# TIDA-010056_Page1.net
KiCad netlist of a schematic drawn in Altium Designer
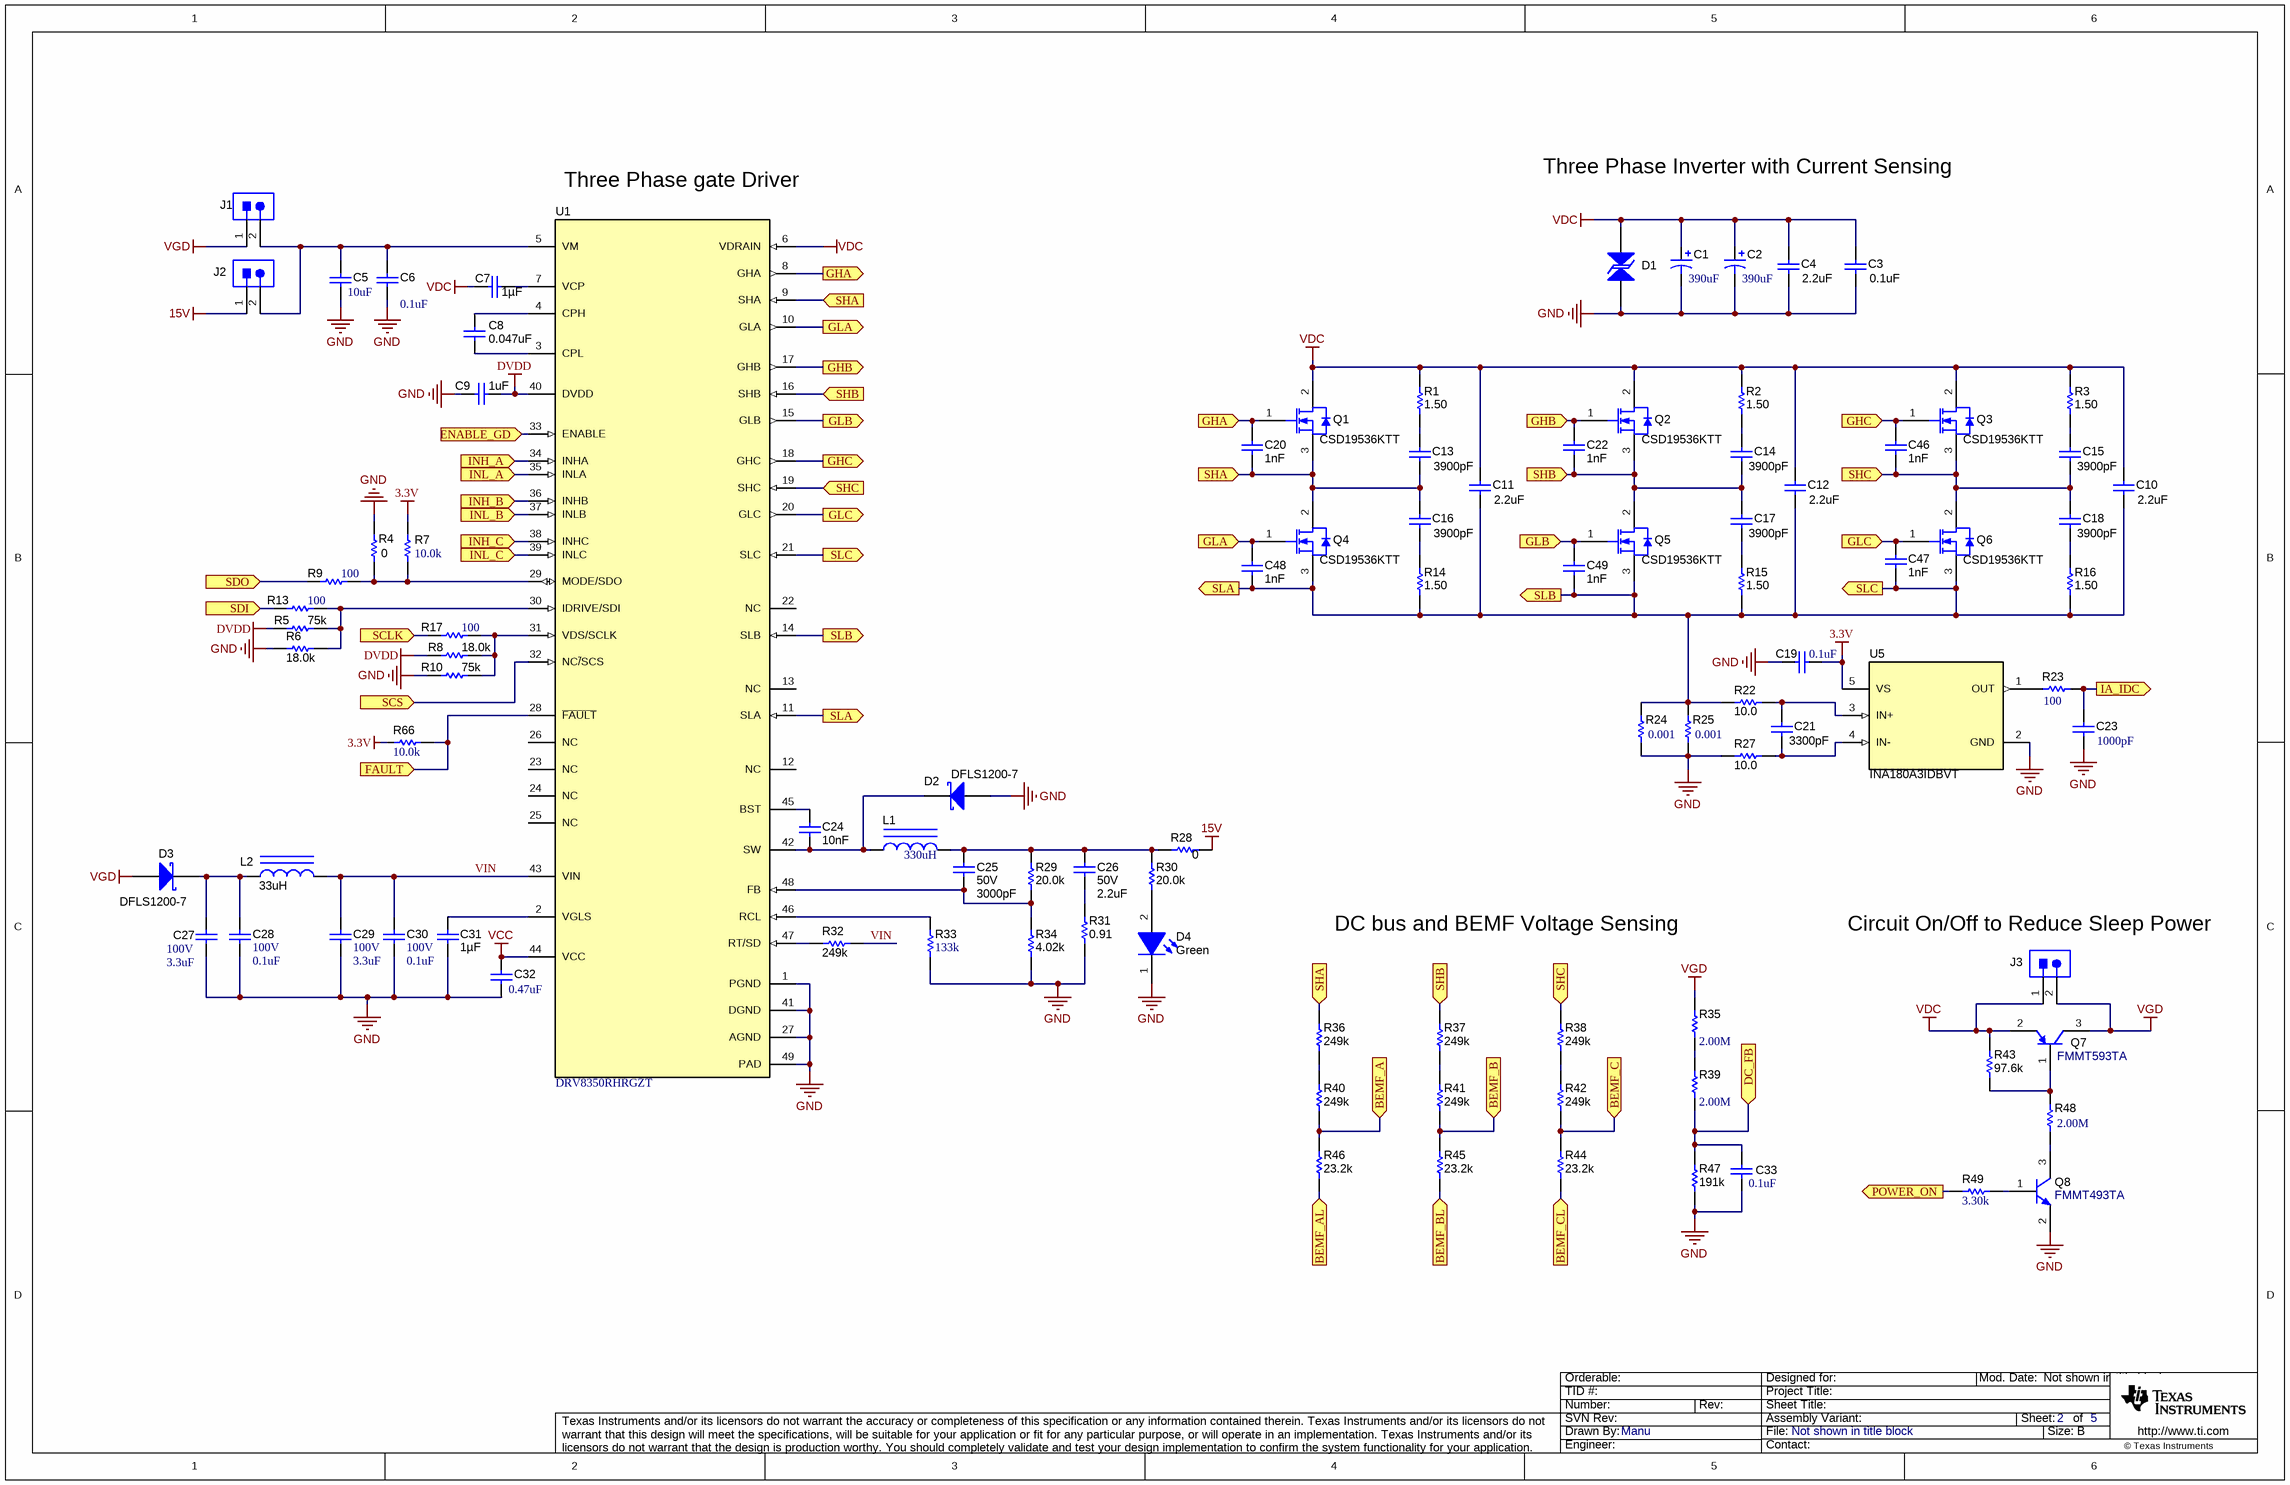
[diagram p0: TIDA-010056_Page1.SchDoc]

(export (version "E")
  (design (tool "Eeschema 10.0.6"))
  (components
    (comp (ref "C1")
      (value "EEU-FS2A391")
      (footprint "YXJ_1600x2500")
      (description "CAP ALUM 390UF 20% 100V THRUHOLE")
      (fields
        (field (name "MANUFACTURER") "Panasonic Electronic Components")
        (field (name "VALUEDISPLAYED") "390uF")
      )
      (libsource (lib "Altium Vault - TI") (part "Cap_Polarized"))
    )
    (comp (ref "C2")
      (value "EEU-FS2A391")
      (footprint "YXJ_1600x2500")
      (description "CAP ALUM 390UF 20% 100V THRUHOLE")
      (fields
        (field (name "MANUFACTURER") "Panasonic Electronic Components")
        (field (name "VALUEDISPLAYED") "390uF")
      )
      (libsource (lib "Altium Vault - TI") (part "Cap_Polarized"))
    )
    (comp (ref "C3")
      (value "C3216X7R2A104K160AA")
      (footprint "1206_180")
      (description "CAP, CERM, 0.1 uF, 100 V, +/- 10%, X7R, 1206")
      (fields (field (name "MANUFACTURER") "TDK") (field (name "VALUEDISPLAYED") "0.1uF"))
      (libsource (lib "Altium Vault - TI") (part "Capacitor"))
    )
    (comp (ref "C4")
      (value "CL31B225KCHSNNE")
      (footprint "1206")
      (description "CAP CER 2.2UF 100V X7R 1206")
      (fields
        (field (name "MANUFACTURER") "Samsung Electro-Mechanics")
        (field (name "VALUEDISPLAYED") "2.2uF")
      )
      (libsource (lib "Altium Vault - TI") (part "Capacitor"))
    )
    (comp (ref "C5")
      (value "22201C106MAT2A")
      (footprint "2220_280")
      (description "CAP, CERM, 10 uF, 100 V, +/- 20%, X7R, 2220")
      (fields (field (name "MANUFACTURER") "AVX") (field (name "VALUEDISPLAYED") "10uF"))
      (libsource (lib "Altium Vault - TI") (part "Capacitor"))
    )
    (comp (ref "C6")
      (value "GRM188R72A104KA35D")
      (footprint "0603")
      (description "CAP, CERM, 0.1 uF, 100 V, +/- 10%, X7R, 0603")
      (fields (field (name "MANUFACTURER") "MuRata") (field (name "VALUEDISPLAYED") "0.1uF"))
      (libsource (lib "Altium Vault - TI") (part "Capacitor"))
    )
    (comp (ref "C7")
      (value "CL05A105MO5NNNC")
      (footprint "0402")
      (description "CAP, CERM, 1 µF, 16 V,+/- 20%, X5R, 0402")
      (fields (field (name "MANUFACTURER") "Samsung Electro-Mechanics") (field (name "VALUEDISPLAYED") "1µF"))
      (libsource (lib "Altium Vault - TI") (part "Capacitor"))
    )
    (comp (ref "C8")
      (value "GRM21BR72A473KA01L")
      (footprint "0805_HV")
      (description "CAP, CERM, 0.047 uF, 100 V, +/- 10%, X7R, 0805")
      (fields (field (name "MANUFACTURER") "MuRata") (field (name "VALUEDISPLAYED") "0.047uF"))
      (libsource (lib "Altium Vault - TI") (part "CMP-0008373-2"))
    )
    (comp (ref "C9")
      (value "GRM152R60J105ME15D")
      (footprint "0402")
      (description "CAP, CERM, 1 uF, 6.3 V, +/- 20%, X5R, 0402")
      (fields (field (name "MANUFACTURER") "MuRata") (field (name "VALUEDISPLAYED") "1uF"))
      (libsource (lib "Altium Vault - TI") (part "CMP-0006372-2"))
    )
    (comp (ref "C10")
      (value "CL31B225KCHSNNE")
      (footprint "1206")
      (description "CAP CER 2.2UF 100V X7R 1206")
      (fields
        (field (name "MANUFACTURER") "Samsung Electro-Mechanics")
        (field (name "VALUEDISPLAYED") "2.2uF")
      )
      (libsource (lib "Altium Vault - TI") (part "Capacitor"))
    )
    (comp (ref "C11")
      (value "CL31B225KCHSNNE")
      (footprint "1206")
      (description "CAP CER 2.2UF 100V X7R 1206")
      (fields
        (field (name "MANUFACTURER") "Samsung Electro-Mechanics")
        (field (name "VALUEDISPLAYED") "2.2uF")
      )
      (libsource (lib "Altium Vault - TI") (part "Capacitor"))
    )
    (comp (ref "C12")
      (value "CL31B225KCHSNNE")
      (footprint "1206")
      (description "CAP CER 2.2UF 100V X7R 1206")
      (fields
        (field (name "MANUFACTURER") "Samsung Electro-Mechanics")
        (field (name "VALUEDISPLAYED") "2.2uF")
      )
      (libsource (lib "Altium Vault - TI") (part "Capacitor"))
    )
    (comp (ref "C13")
      (value "12061C392KAZ2A")
      (footprint "1206")
      (description "CAP CER 3900PF 100V X7R 1206")
      (fields (field (name "MANUFACTURER") "AVX Corporation") (field (name "VALUEDISPLAYED") "3900pF"))
      (libsource (lib "Altium Vault - TI") (part "Capacitor"))
    )
    (comp (ref "C14")
      (value "12061C392KAZ2A")
      (footprint "1206")
      (description "CAP CER 3900PF 100V X7R 1206")
      (fields (field (name "MANUFACTURER") "AVX Corporation") (field (name "VALUEDISPLAYED") "3900pF"))
      (libsource (lib "Altium Vault - TI") (part "Capacitor"))
    )
    (comp (ref "C15")
      (value "12061C392KAZ2A")
      (footprint "1206")
      (description "CAP CER 3900PF 100V X7R 1206")
      (fields (field (name "MANUFACTURER") "AVX Corporation") (field (name "VALUEDISPLAYED") "3900pF"))
      (libsource (lib "Altium Vault - TI") (part "Capacitor"))
    )
    (comp (ref "C16")
      (value "12061C392KAZ2A")
      (footprint "1206")
      (description "CAP CER 3900PF 100V X7R 1206")
      (fields (field (name "MANUFACTURER") "AVX Corporation") (field (name "VALUEDISPLAYED") "3900pF"))
      (libsource (lib "Altium Vault - TI") (part "Capacitor"))
    )
    (comp (ref "C17")
      (value "12061C392KAZ2A")
      (footprint "1206")
      (description "CAP CER 3900PF 100V X7R 1206")
      (fields (field (name "MANUFACTURER") "AVX Corporation") (field (name "VALUEDISPLAYED") "3900pF"))
      (libsource (lib "Altium Vault - TI") (part "Capacitor"))
    )
    (comp (ref "C18")
      (value "12061C392KAZ2A")
      (footprint "1206")
      (description "CAP CER 3900PF 100V X7R 1206")
      (fields (field (name "MANUFACTURER") "AVX Corporation") (field (name "VALUEDISPLAYED") "3900pF"))
      (libsource (lib "Altium Vault - TI") (part "Capacitor"))
    )
    (comp (ref "C19")
      (value "GCM155R71A104KA55D")
      (footprint "0402")
      (description "CAP, CERM, 0.1 uF, 10 V, +/- 10%, X7R, AEC-Q200 Grade 1, 0402")
      (fields (field (name "MANUFACTURER") "MuRata") (field (name "VALUEDISPLAYED") "0.1uF"))
      (libsource (lib "Altium Vault - TI") (part "Capacitor"))
    )
    (comp (ref "C20")
      (value "885012206083")
      (footprint "0603")
      (description "CAP, CERM, 1000 pF, 50 V,+/- 10%, X7R, 0603")
      (fields (field (name "MANUFACTURER") "Wurth Elektronik") (field (name "CAP_F") "1nF"))
      (libsource (lib "Altium Vault - TI") (part "Capacitor"))
    )
    (comp (ref "C21")
      (value "GRM155R71H332KA01D")
      (footprint "0402")
      (description "CAP, CERM, 3300 pF, 50 V, +/- 10%, X7R, 0402")
      (fields (field (name "MANUFACTURER") "MuRata") (field (name "VALUEDISPLAYED") "3300pF"))
      (libsource (lib "Altium Vault - TI") (part "Capacitor"))
    )
    (comp (ref "C22")
      (value "885012206083")
      (footprint "0603")
      (description "CAP, CERM, 1000 pF, 50 V,+/- 10%, X7R, 0603")
      (fields (field (name "MANUFACTURER") "Wurth Elektronik") (field (name "CAP_F") "1nF"))
      (libsource (lib "Altium Vault - TI") (part "Capacitor"))
    )
    (comp (ref "C23")
      (value "GRM155R71C102KA01D")
      (footprint "0402")
      (description "CAP, CERM, 1000 pF, 16 V, +/- 10%, X7R, 0402")
      (fields (field (name "MANUFACTURER") "MuRata") (field (name "VALUEDISPLAYED") "1000pF"))
      (libsource (lib "Altium Vault - TI") (part "Capacitor"))
    )
    (comp (ref "C24")
      (value "885012206114")
      (footprint "0603")
      (description "CAP, CERM, 0.01 µF, 100 V,+/- 10%, X7R, 0603")
      (fields (field (name "MANUFACTURER") "Wurth Elektronik") (field (name "CAP_F") "10nF"))
      (libsource (lib "Altium Vault - TI") (part "Capacitor"))
    )
    (comp (ref "C25")
      (value "GRM1885C1H302JA01D")
      (footprint "0603")
      (description "CAP, CERM, 3000 pF, 50 V, +/- 5%, C0G/NP0, 0603")
      (fields
        (field (name "MANUFACTURER") "MuRata")
        (field (name "VDC_V") "50V")
        (field (name "VALUEDISPLAYED") "3000pF")
      )
      (libsource (lib "Altium Vault - TI") (part "Capacitor"))
    )
    (comp (ref "C26")
      (value "C2012X7R1H225K125AC")
      (footprint "0805_HV")
      (description "CAP, CERM, 2.2 uF, 50 V, +/- 10%, X7R, 0805")
      (fields
        (field (name "MANUFACTURER") "TDK")
        (field (name "VDC_V") "50V")
        (field (name "VALUEDISPLAYED") "2.2uF")
      )
      (libsource (lib "Altium Vault - TI") (part "Capacitor"))
    )
    (comp (ref "C27")
      (value "C3216X7S2A335M160AB")
      (footprint "1206_190")
      (description "CAP, CERM, 3.3 uF, 100 V, +/- 20%, X7S, 1206_190")
      (fields
        (field (name "MANUFACTURER") "TDK")
        (field (name "VDC_V") "100V")
        (field (name "VALUEDISPLAYED") "3.3uF")
      )
      (libsource (lib "Altium Vault - TI") (part "Capacitor"))
    )
    (comp (ref "C28")
      (value "GRM188R72A104KA35D")
      (footprint "0603")
      (description "CAP, CERM, 0.1 uF, 100 V, +/- 10%, X7R, 0603")
      (fields
        (field (name "MANUFACTURER") "MuRata")
        (field (name "VDC_V") "100V")
        (field (name "VALUEDISPLAYED") "0.1uF")
      )
      (libsource (lib "Altium Vault - TI") (part "Capacitor"))
    )
    (comp (ref "C29")
      (value "C3216X7S2A335M160AB")
      (footprint "1206_190")
      (description "CAP, CERM, 3.3 uF, 100 V, +/- 20%, X7S, 1206_190")
      (fields
        (field (name "MANUFACTURER") "TDK")
        (field (name "VDC_V") "100V")
        (field (name "VALUEDISPLAYED") "3.3uF")
      )
      (libsource (lib "Altium Vault - TI") (part "Capacitor"))
    )
    (comp (ref "C30")
      (value "GRM188R72A104KA35D")
      (footprint "0603")
      (description "CAP, CERM, 0.1 uF, 100 V, +/- 10%, X7R, 0603")
      (fields
        (field (name "MANUFACTURER") "MuRata")
        (field (name "VDC_V") "100V")
        (field (name "VALUEDISPLAYED") "0.1uF")
      )
      (libsource (lib "Altium Vault - TI") (part "Capacitor"))
    )
    (comp (ref "C31")
      (value "CL05A105MO5NNNC")
      (footprint "0402")
      (description "CAP, CERM, 1 µF, 16 V,+/- 20%, X5R, 0402")
      (fields (field (name "MANUFACTURER") "Samsung Electro-Mechanics") (field (name "VALUEDISPLAYED") "1µF"))
      (libsource (lib "Altium Vault - TI") (part "Capacitor"))
    )
    (comp (ref "C32")
      (value "CGB2A1X5R1C474K033BC")
      (footprint "0402")
      (description "CAP CER 0.47UF 16V X5R 0402")
      (fields (field (name "MANUFACTURER") "TDK Corporation") (field (name "VALUEDISPLAYED") "0.47uF"))
      (libsource (lib "Altium Vault - TI") (part "Capacitor"))
    )
    (comp (ref "C33")
      (value "GCM155R71A104KA55D")
      (footprint "0402")
      (description "CAP, CERM, 0.1 uF, 10 V, +/- 10%, X7R, AEC-Q200 Grade 1, 0402")
      (fields (field (name "MANUFACTURER") "MuRata") (field (name "VALUEDISPLAYED") "0.1uF"))
      (libsource (lib "Altium Vault - TI") (part "Capacitor"))
    )
    (comp (ref "C46")
      (value "885012206083")
      (footprint "0603")
      (description "CAP, CERM, 1000 pF, 50 V,+/- 10%, X7R, 0603")
      (fields (field (name "MANUFACTURER") "Wurth Elektronik") (field (name "CAP_F") "1nF"))
      (libsource (lib "Altium Vault - TI") (part "Capacitor"))
    )
    (comp (ref "C47")
      (value "885012206083")
      (footprint "0603")
      (description "CAP, CERM, 1000 pF, 50 V,+/- 10%, X7R, 0603")
      (fields (field (name "MANUFACTURER") "Wurth Elektronik") (field (name "CAP_F") "1nF"))
      (libsource (lib "Altium Vault - TI") (part "Capacitor"))
    )
    (comp (ref "C48")
      (value "885012206083")
      (footprint "0603")
      (description "CAP, CERM, 1000 pF, 50 V,+/- 10%, X7R, 0603")
      (fields (field (name "MANUFACTURER") "Wurth Elektronik") (field (name "CAP_F") "1nF"))
      (libsource (lib "Altium Vault - TI") (part "Capacitor"))
    )
    (comp (ref "C49")
      (value "885012206083")
      (footprint "0603")
      (description "CAP, CERM, 1000 pF, 50 V,+/- 10%, X7R, 0603")
      (fields (field (name "MANUFACTURER") "Wurth Elektronik") (field (name "CAP_F") "1nF"))
      (libsource (lib "Altium Vault - TI") (part "Capacitor"))
    )
    (comp (ref "D1")
      (value "SMBJ70CA-13-F")
      (footprint "SMB-Bi")
      (description "Diode, TVS, Bi, 70 V, SMB")
      (fields (field (name "MANUFACTURER") "Diodes Inc."))
      (libsource (lib "Altium Vault - TI") (part "Diode_TVS_Bi"))
    )
    (comp (ref "D2")
      (value "DFLS1200-7")
      (footprint "PowerDI123")
      (description "Diode, Schottky, 200 V, 1 A, PowerDI123")
      (fields (field (name "MANUFACTURER") "Diodes Inc."))
      (libsource (lib "Altium Vault - TI") (part "DIODE_SCHOTTKY"))
    )
    (comp (ref "D3")
      (value "DFLS1200-7")
      (footprint "PowerDI123")
      (description "Diode, Schottky, 200 V, 1 A, PowerDI123")
      (fields (field (name "MANUFACTURER") "Diodes Inc."))
      (libsource (lib "Altium Vault - TI") (part "DIODE_SCHOTTKY"))
    )
    (comp (ref "D4")
      (value "Green")
      (footprint "WL-SMCW_GREEN")
      (description "LED, Green, SMD")
      (fields (field (name "MANUFACTURER") "Wurth Elektronik") (field (name "PARTNUMBER") "150060GS75000"))
      (libsource (lib "Altium Vault - TI") (part "LED_A2_K1"))
    )
    (comp (ref "J1")
      (value "61300211121")
      (footprint "WURTH_61300211121")
      (description "Header, 2.54 mm, 2x1, Gold, TH")
      (fields (field (name "MANUFACTURER") "Wurth Elektronik"))
      (libsource (lib "Altium Vault - TI") (part "Header_2x1"))
    )
    (comp (ref "J2")
      (value "61300211121")
      (footprint "WURTH_61300211121")
      (description "Header, 2.54 mm, 2x1, Gold, TH")
      (fields (field (name "MANUFACTURER") "Wurth Elektronik"))
      (libsource (lib "Altium Vault - TI") (part "Header_2x1"))
    )
    (comp (ref "J3")
      (value "61300211121")
      (footprint "WURTH_61300211121")
      (description "Header, 2.54 mm, 2x1, Gold, TH")
      (fields (field (name "MANUFACTURER") "Wurth Elektronik"))
      (libsource (lib "Altium Vault - TI") (part "Header_2x1"))
    )
    (comp (ref "L1")
      (value "SDR0604-331KL")
      (footprint "SDR0604")
      (description "Inductor, Drum Core, Ferrite, 330 uH, 0.27 A, 2.25 ohm, SMD")
      (fields (field (name "MANUFACTURER") "Bourns") (field (name "VALUEDISPLAYED") "330uH"))
      (libsource (lib "Altium Vault - TI") (part "Inductor_Iron"))
    )
    (comp (ref "L2")
      (value "Inductor_Iron")
      (footprint "NLCV25")
      (description "Inductor, Shielded, Ferrite, 33 uH, 0.085 A, 1.4 ohm, SMD")
      (fields
        (field (name "PARTNUMBER") "NLFV25T-330K-PF")
        (field (name "VALUEDISPLAYED") "33uH")
        (field (name "MANUFACTURER") "TDK")
      )
      (libsource (lib "Altium Vault - TI") (part "Inductor_Iron"))
    )
    (comp (ref "Q1")
      (value "CSD19536KTT")
      (footprint "KTT0002A")
      (description "MOSFET, N-CH, 100 V, 200 A, KTT0002A (TO-263-2)")
      (fields (field (name "MANUFACTURER") "Texas Instruments"))
      (libsource (lib "Altium Vault - TI") (part "MOSFET_N_D2G1S3"))
    )
    (comp (ref "Q2")
      (value "CSD19536KTT")
      (footprint "KTT0002A")
      (description "MOSFET, N-CH, 100 V, 200 A, KTT0002A (TO-263-2)")
      (fields (field (name "MANUFACTURER") "Texas Instruments"))
      (libsource (lib "Altium Vault - TI") (part "MOSFET_N_D2G1S3"))
    )
    (comp (ref "Q3")
      (value "CSD19536KTT")
      (footprint "KTT0002A")
      (description "MOSFET, N-CH, 100 V, 200 A, KTT0002A (TO-263-2)")
      (fields (field (name "MANUFACTURER") "Texas Instruments"))
      (libsource (lib "Altium Vault - TI") (part "MOSFET_N_D2G1S3"))
    )
    (comp (ref "Q4")
      (value "CSD19536KTT")
      (footprint "KTT0002A")
      (description "MOSFET, N-CH, 100 V, 200 A, KTT0002A (TO-263-2)")
      (fields (field (name "MANUFACTURER") "Texas Instruments"))
      (libsource (lib "Altium Vault - TI") (part "MOSFET_N_D2G1S3"))
    )
    (comp (ref "Q5")
      (value "CSD19536KTT")
      (footprint "KTT0002A")
      (description "MOSFET, N-CH, 100 V, 200 A, KTT0002A (TO-263-2)")
      (fields (field (name "MANUFACTURER") "Texas Instruments"))
      (libsource (lib "Altium Vault - TI") (part "MOSFET_N_D2G1S3"))
    )
    (comp (ref "Q6")
      (value "CSD19536KTT")
      (footprint "KTT0002A")
      (description "MOSFET, N-CH, 100 V, 200 A, KTT0002A (TO-263-2)")
      (fields (field (name "MANUFACTURER") "Texas Instruments"))
      (libsource (lib "Altium Vault - TI") (part "MOSFET_N_D2G1S3"))
    )
    (comp (ref "Q7")
      (value "FMMT593TA")
      (footprint "SOT-23")
      (description "TRANS PNP 100V 1A SOT23-3")
      (fields (field (name "MANUFACTURER") "Fairchild Semiconductor"))
      (libsource (lib "Altium Vault - TI") (part "BJT_PNP_C3B1E2"))
    )
    (comp (ref "Q8")
      (value "FMMT493TA")
      (footprint "SOT-23")
      (description "TRANS NPN 100V 1A SOT23-3")
      (fields (field (name "MANUFACTURER") "Diodes Incorporated"))
      (libsource (lib "Altium Vault - TI") (part "BJT_NPN_C3B1E2"))
    )
    (comp (ref "R1")
      (value "CRCW12061R50FKEA")
      (footprint "1206")
      (description "RES, 1.50, 1%, 0.25 W, AEC-Q200 Grade 0, 1206")
      (fields (field (name "MANUFACTURER") "Vishay-Dale") (field (name "VALUEDISPLAYED") "1.50"))
      (libsource (lib "Altium Vault - TI") (part "Resistor"))
    )
    (comp (ref "R2")
      (value "CRCW12061R50FKEA")
      (footprint "1206")
      (description "RES, 1.50, 1%, 0.25 W, AEC-Q200 Grade 0, 1206")
      (fields (field (name "MANUFACTURER") "Vishay-Dale") (field (name "VALUEDISPLAYED") "1.50"))
      (libsource (lib "Altium Vault - TI") (part "Resistor"))
    )
    (comp (ref "R3")
      (value "CRCW12061R50FKEA")
      (footprint "1206")
      (description "RES, 1.50, 1%, 0.25 W, AEC-Q200 Grade 0, 1206")
      (fields (field (name "MANUFACTURER") "Vishay-Dale") (field (name "VALUEDISPLAYED") "1.50"))
      (libsource (lib "Altium Vault - TI") (part "Resistor"))
    )
    (comp (ref "R4")
      (value "RC0402JR-070RL")
      (footprint "0402")
      (description "RES, 0, 5%, 0.063 W, 0402")
      (fields (field (name "MANUFACTURER") "Yageo America") (field (name "VALUEDISPLAYED") "0"))
      (libsource (lib "Altium Vault - TI") (part "Resistor"))
    )
    (comp (ref "R5")
      (value "CRCW040275K0JNED")
      (footprint "0402")
      (description "RES, 75 k, 5%, 0.063 W, AEC-Q200 Grade 0, 0402")
      (fields (field (name "MANUFACTURER") "Vishay-Dale") (field (name "VALUEDISPLAYED") "75k"))
      (libsource (lib "Altium Vault - TI") (part "Resistor"))
    )
    (comp (ref "R6")
      (value "ERJ-2RKF1802X")
      (footprint "0402")
      (description "RES, 18.0 k, 1%, 0.1 W, AEC-Q200 Grade 0, 0402")
      (fields (field (name "MANUFACTURER") "Panasonic") (field (name "VALUEDISPLAYED") "18.0k"))
      (libsource (lib "Altium Vault - TI") (part "Resistor"))
    )
    (comp (ref "R7")
      (value "ERJ-2RKF1002X")
      (footprint "0402")
      (description "RES, 10.0 k, 1%, 0.1 W, 0402")
      (fields (field (name "MANUFACTURER") "Panasonic") (field (name "VALUEDISPLAYED") "10.0k"))
      (libsource (lib "Altium Vault - TI") (part "Resistor"))
    )
    (comp (ref "R8")
      (value "ERJ-2RKF1802X")
      (footprint "0402")
      (description "RES, 18.0 k, 1%, 0.1 W, AEC-Q200 Grade 0, 0402")
      (fields (field (name "MANUFACTURER") "Panasonic") (field (name "VALUEDISPLAYED") "18.0k"))
      (libsource (lib "Altium Vault - TI") (part "Resistor"))
    )
    (comp (ref "R9")
      (value "ERJ-2GEJ101X")
      (footprint "0402")
      (description "RES, 100, 5%, 0.1 W, AEC-Q200 Grade 0, 0402")
      (fields (field (name "MANUFACTURER") "Panasonic") (field (name "VALUEDISPLAYED") "100"))
      (libsource (lib "Altium Vault - TI") (part "Resistor"))
    )
    (comp (ref "R10")
      (value "CRCW040275K0JNED")
      (footprint "0402")
      (description "RES, 75 k, 5%, 0.063 W, AEC-Q200 Grade 0, 0402")
      (fields (field (name "MANUFACTURER") "Vishay-Dale") (field (name "VALUEDISPLAYED") "75k"))
      (libsource (lib "Altium Vault - TI") (part "Resistor"))
    )
    (comp (ref "R13")
      (value "ERJ-2GEJ101X")
      (footprint "0402")
      (description "RES, 100, 5%, 0.1 W, AEC-Q200 Grade 0, 0402")
      (fields (field (name "MANUFACTURER") "Panasonic") (field (name "VALUEDISPLAYED") "100"))
      (libsource (lib "Altium Vault - TI") (part "Resistor"))
    )
    (comp (ref "R14")
      (value "CRCW12061R50FKEA")
      (footprint "1206")
      (description "RES, 1.50, 1%, 0.25 W, AEC-Q200 Grade 0, 1206")
      (fields (field (name "MANUFACTURER") "Vishay-Dale") (field (name "VALUEDISPLAYED") "1.50"))
      (libsource (lib "Altium Vault - TI") (part "Resistor"))
    )
    (comp (ref "R15")
      (value "CRCW12061R50FKEA")
      (footprint "1206")
      (description "RES, 1.50, 1%, 0.25 W, AEC-Q200 Grade 0, 1206")
      (fields (field (name "MANUFACTURER") "Vishay-Dale") (field (name "VALUEDISPLAYED") "1.50"))
      (libsource (lib "Altium Vault - TI") (part "Resistor"))
    )
    (comp (ref "R16")
      (value "CRCW12061R50FKEA")
      (footprint "1206")
      (description "RES, 1.50, 1%, 0.25 W, AEC-Q200 Grade 0, 1206")
      (fields (field (name "MANUFACTURER") "Vishay-Dale") (field (name "VALUEDISPLAYED") "1.50"))
      (libsource (lib "Altium Vault - TI") (part "Resistor"))
    )
    (comp (ref "R17")
      (value "ERJ-2GEJ101X")
      (footprint "0402")
      (description "RES, 100, 5%, 0.1 W, AEC-Q200 Grade 0, 0402")
      (fields (field (name "MANUFACTURER") "Panasonic") (field (name "VALUEDISPLAYED") "100"))
      (libsource (lib "Altium Vault - TI") (part "Resistor"))
    )
    (comp (ref "R22")
      (value "CRCW040210R0FKED")
      (footprint "0402")
      (description "RES, 10.0, 1%, 0.063 W, AEC-Q200 Grade 0, 0402")
      (fields (field (name "MANUFACTURER") "Vishay-Dale") (field (name "VALUEDISPLAYED") "10.0"))
      (libsource (lib "Altium Vault - TI") (part "Resistor"))
    )
    (comp (ref "R23")
      (value "ERJ-2GEJ101X")
      (footprint "0402")
      (description "RES, 100, 5%, 0.1 W, AEC-Q200 Grade 0, 0402")
      (fields (field (name "MANUFACTURER") "Panasonic") (field (name "VALUEDISPLAYED") "100"))
      (libsource (lib "Altium Vault - TI") (part "Resistor"))
    )
    (comp (ref "R24")
      (value "CRE2512-FZ-R001E-3")
      (footprint "CRE2512-R1_R4")
      (description "RES, 0.001, 1%, 3 W, AEC-Q200 Grade 0, 2512")
      (fields (field (name "MANUFACTURER") "Bourns") (field (name "VALUEDISPLAYED") "0.001"))
      (libsource (lib "Altium Vault - TI") (part "Resistor"))
    )
    (comp (ref "R25")
      (value "0.001")
      (footprint "CRE2512-R1_R4")
      (description "RES, 0.001, 1%, 3 W, AEC-Q200 Grade 0, 2512")
      (fields (field (name "MANUFACTURER") "Bourns") (field (name "PARTNUMBER") "CRE2512-FZ-R001E-3"))
      (libsource (lib "Altium Vault - TI") (part "Resistor"))
    )
    (comp (ref "R27")
      (value "CRCW040210R0FKED")
      (footprint "0402")
      (description "RES, 10.0, 1%, 0.063 W, AEC-Q200 Grade 0, 0402")
      (fields (field (name "MANUFACTURER") "Vishay-Dale") (field (name "VALUEDISPLAYED") "10.0"))
      (libsource (lib "Altium Vault - TI") (part "Resistor"))
    )
    (comp (ref "R28")
      (value "RC0402JR-070RL")
      (footprint "0402")
      (description "RES, 0, 5%, 0.063 W, 0402")
      (fields (field (name "MANUFACTURER") "Yageo America") (field (name "VALUEDISPLAYED") "0"))
      (libsource (lib "Altium Vault - TI") (part "Resistor"))
    )
    (comp (ref "R29")
      (value "CRCW040220K0FKED")
      (footprint "0402")
      (description "RES, 20.0 k, 1%, 0.063 W, AEC-Q200 Grade 0, 0402")
      (fields (field (name "MANUFACTURER") "Vishay-Dale") (field (name "VALUEDISPLAYED") "20.0k"))
      (libsource (lib "Altium Vault - TI") (part "Resistor"))
    )
    (comp (ref "R30")
      (value "CRCW040220K0FKED")
      (footprint "0402")
      (description "RES, 20.0 k, 1%, 0.063 W, AEC-Q200 Grade 0, 0402")
      (fields (field (name "MANUFACTURER") "Vishay-Dale") (field (name "VALUEDISPLAYED") "20.0k"))
      (libsource (lib "Altium Vault - TI") (part "Resistor"))
    )
    (comp (ref "R31")
      (value "ERJ-2BQFR91X")
      (footprint "0402")
      (description "RES, 0.91, 1%, 0.125 W, 0402")
      (fields (field (name "MANUFACTURER") "Panasonic") (field (name "VALUEDISPLAYED") "0.91"))
      (libsource (lib "Altium Vault - TI") (part "Resistor"))
    )
    (comp (ref "R32")
      (value "RC0402FR-07249KL")
      (footprint "0402")
      (description "RES SMD 249K OHM 1% 1/16W 0402")
      (fields (field (name "MANUFACTURER") "Yageo") (field (name "VALUEDISPLAYED") "249k"))
      (libsource (lib "Altium Vault - TI") (part "Resistor"))
    )
    (comp (ref "R33")
      (value "AC0402FR-07133KL")
      (footprint "0402")
      (description "RES, 133 k, 1%, 0.063 W, AEC-Q200 Grade 0, 0402")
      (fields (field (name "MANUFACTURER") "Yageo America") (field (name "VALUEDISPLAYED") "133k"))
      (libsource (lib "Altium Vault - TI") (part "Resistor"))
    )
    (comp (ref "R34")
      (value "RC0402FR-074K02L")
      (footprint "0402")
      (description "RES SMD 4.02K OHM 1% 1/16W 0402")
      (fields (field (name "MANUFACTURER") "Yageo") (field (name "VALUEDISPLAYED") "4.02k"))
      (libsource (lib "Altium Vault - TI") (part "Resistor"))
    )
    (comp (ref "R35")
      (value "CRCW04022M00FKED")
      (footprint "0402")
      (description "RES, 2.00 M, 1%, 0.063 W, AEC-Q200 Grade 0, 0402")
      (fields (field (name "MANUFACTURER") "Vishay-Dale") (field (name "VALUEDISPLAYED") "2.00M"))
      (libsource (lib "Altium Vault - TI") (part "Resistor"))
    )
    (comp (ref "R36")
      (value "RC0402FR-07249KL")
      (footprint "0402")
      (description "RES SMD 249K OHM 1% 1/16W 0402")
      (fields (field (name "MANUFACTURER") "Yageo") (field (name "VALUEDISPLAYED") "249k"))
      (libsource (lib "Altium Vault - TI") (part "Resistor"))
    )
    (comp (ref "R37")
      (value "RC0402FR-07249KL")
      (footprint "0402")
      (description "RES SMD 249K OHM 1% 1/16W 0402")
      (fields (field (name "MANUFACTURER") "Yageo") (field (name "VALUEDISPLAYED") "249k"))
      (libsource (lib "Altium Vault - TI") (part "Resistor"))
    )
    (comp (ref "R38")
      (value "RC0402FR-07249KL")
      (footprint "0402")
      (description "RES SMD 249K OHM 1% 1/16W 0402")
      (fields (field (name "MANUFACTURER") "Yageo") (field (name "VALUEDISPLAYED") "249k"))
      (libsource (lib "Altium Vault - TI") (part "Resistor"))
    )
    (comp (ref "R39")
      (value "CRCW04022M00FKED")
      (footprint "0402")
      (description "RES, 2.00 M, 1%, 0.063 W, AEC-Q200 Grade 0, 0402")
      (fields (field (name "MANUFACTURER") "Vishay-Dale") (field (name "VALUEDISPLAYED") "2.00M"))
      (libsource (lib "Altium Vault - TI") (part "Resistor"))
    )
    (comp (ref "R40")
      (value "RC0402FR-07249KL")
      (footprint "0402")
      (description "RES SMD 249K OHM 1% 1/16W 0402")
      (fields (field (name "MANUFACTURER") "Yageo") (field (name "VALUEDISPLAYED") "249k"))
      (libsource (lib "Altium Vault - TI") (part "Resistor"))
    )
    (comp (ref "R41")
      (value "RC0402FR-07249KL")
      (footprint "0402")
      (description "RES SMD 249K OHM 1% 1/16W 0402")
      (fields (field (name "MANUFACTURER") "Yageo") (field (name "VALUEDISPLAYED") "249k"))
      (libsource (lib "Altium Vault - TI") (part "Resistor"))
    )
    (comp (ref "R42")
      (value "RC0402FR-07249KL")
      (footprint "0402")
      (description "RES SMD 249K OHM 1% 1/16W 0402")
      (fields (field (name "MANUFACTURER") "Yageo") (field (name "VALUEDISPLAYED") "249k"))
      (libsource (lib "Altium Vault - TI") (part "Resistor"))
    )
    (comp (ref "R43")
      (value "ERJ-2RKF9762X")
      (footprint "0402")
      (description "RES, 97.6 k, 1%, 0.1 W, AEC-Q200 Grade 0, 0402")
      (fields (field (name "MANUFACTURER") "Panasonic") (field (name "VALUEDISPLAYED") "97.6k"))
      (libsource (lib "Altium Vault - TI") (part "Resistor"))
    )
    (comp (ref "R44")
      (value "RC0402FR-0723K2L")
      (footprint "0402")
      (description "RES SMD 23.2K OHM 1% 1/16W 0402")
      (fields (field (name "MANUFACTURER") "Yageo") (field (name "VALUEDISPLAYED") "23.2k"))
      (libsource (lib "Altium Vault - TI") (part "Resistor"))
    )
    (comp (ref "R45")
      (value "RC0402FR-0723K2L")
      (footprint "0402")
      (description "RES SMD 23.2K OHM 1% 1/16W 0402")
      (fields (field (name "MANUFACTURER") "Yageo") (field (name "VALUEDISPLAYED") "23.2k"))
      (libsource (lib "Altium Vault - TI") (part "Resistor"))
    )
    (comp (ref "R46")
      (value "RC0402FR-0723K2L")
      (footprint "0402")
      (description "RES SMD 23.2K OHM 1% 1/16W 0402")
      (fields (field (name "MANUFACTURER") "Yageo") (field (name "VALUEDISPLAYED") "23.2k"))
      (libsource (lib "Altium Vault - TI") (part "Resistor"))
    )
    (comp (ref "R47")
      (value "ERJ-2RKF1913X")
      (footprint "0402")
      (description "RES, 191 k, 1%, 0.1 W, AEC-Q200 Grade 0, 0402")
      (fields (field (name "MANUFACTURER") "Panasonic") (field (name "VALUEDISPLAYED") "191k"))
      (libsource (lib "Altium Vault - TI") (part "Resistor"))
    )
    (comp (ref "R48")
      (value "CRCW04022M00FKED")
      (footprint "0402")
      (description "RES, 2.00 M, 1%, 0.063 W, AEC-Q200 Grade 0, 0402")
      (fields (field (name "MANUFACTURER") "Vishay-Dale") (field (name "VALUEDISPLAYED") "2.00M"))
      (libsource (lib "Altium Vault - TI") (part "Resistor"))
    )
    (comp (ref "R49")
      (value "ERJ-2RKF3301X")
      (footprint "0402")
      (description "RES, 3.30 k, 1%, 0.1 W, AEC-Q200 Grade 0, 0402")
      (fields (field (name "MANUFACTURER") "Panasonic") (field (name "VALUEDISPLAYED") "3.30k"))
      (libsource (lib "Altium Vault - TI") (part "Resistor"))
    )
    (comp (ref "R66")
      (value "ERJ-2RKF1002X")
      (footprint "0402")
      (description "RES, 10.0 k, 1%, 0.1 W, 0402")
      (fields (field (name "MANUFACTURER") "Panasonic") (field (name "VALUEDISPLAYED") "10.0k"))
      (libsource (lib "Altium Vault - TI") (part "Resistor"))
    )
    (comp (ref "U1")
      (value "DRV8350RHRGZT")
      (footprint "RGZ0048L")
      (description "100-V Three-Phase Smart Gate Driver With Buck Regulator, RGZ0048L (VQFN-48)")
      (fields (field (name "PARTNUMBER") "DRV8350RHRGZT") (field (name "MANUFACTURER") "Texas Instruments"))
      (libsource (lib "Altium Vault - TI") (part "DRV8350R"))
    )
    (comp (ref "U5")
      (value "INA180A3IDBV")
      (footprint "DBV0005A_N")
      (fields (field (name "MANUFACTURER") "Texas Instruments") (field (name "PARTNUMBER") "INA180A3IDBVT"))
      (libsource (lib "Altium Vault - TI") (part "INA180"))
    )
  )
  (nets
    (net (code "1") (name "/BEMF_A") (class "Default")
      (node (ref "R40") (pin "1") (pinfunction "1_1") (pintype "passive"))
      (node (ref "R46") (pin "2") (pinfunction "2_2") (pintype "passive"))
    )
    (net (code "2") (name "/BEMF_AL") (class "Default")
      (node (ref "R46") (pin "1") (pinfunction "1_1") (pintype "passive"))
    )
    (net (code "3") (name "/BEMF_B") (class "Default")
      (node (ref "R41") (pin "1") (pinfunction "1_1") (pintype "passive"))
      (node (ref "R45") (pin "2") (pinfunction "2_2") (pintype "passive"))
    )
    (net (code "4") (name "/BEMF_BL") (class "Default")
      (node (ref "R45") (pin "1") (pinfunction "1_1") (pintype "passive"))
    )
    (net (code "5") (name "/BEMF_C") (class "Default")
      (node (ref "R42") (pin "1") (pinfunction "1_1") (pintype "passive"))
      (node (ref "R44") (pin "2") (pinfunction "2_2") (pintype "passive"))
    )
    (net (code "6") (name "/BEMF_CL") (class "Default")
      (node (ref "R44") (pin "1") (pinfunction "1_1") (pintype "passive"))
    )
    (net (code "7") (name "/DC_FB") (class "Default")
      (node (ref "C33") (pin "1") (pinfunction "1_1") (pintype "passive"))
      (node (ref "R39") (pin "1") (pinfunction "1_1") (pintype "passive"))
      (node (ref "R47") (pin "2") (pinfunction "2_2") (pintype "passive"))
    )
    (net (code "8") (name "/ENABLE_GD") (class "Default")
      (node (ref "U1") (pin "33") (pinfunction "ENABLE_33") (pintype "input"))
    )
    (net (code "9") (name "/FAULT") (class "Default")
      (node (ref "R66") (pin "1") (pinfunction "1_1") (pintype "passive"))
      (node (ref "U1") (pin "28") (pinfunction "FAULT_28") (pintype "open_collector"))
    )
    (net (code "10") (name "/GHA") (class "Default")
      (node (ref "C20") (pin "1") (pinfunction "1_1") (pintype "passive"))
      (node (ref "Q1") (pin "1") (pinfunction "G_1") (pintype "passive"))
      (node (ref "U1") (pin "8") (pinfunction "GHA_8") (pintype "output"))
    )
    (net (code "11") (name "/GHB") (class "Default")
      (node (ref "C22") (pin "1") (pinfunction "1_1") (pintype "passive"))
      (node (ref "Q2") (pin "1") (pinfunction "G_1") (pintype "passive"))
      (node (ref "U1") (pin "17") (pinfunction "GHB_17") (pintype "output"))
    )
    (net (code "12") (name "/GHC") (class "Default")
      (node (ref "C46") (pin "1") (pinfunction "1_1") (pintype "passive"))
      (node (ref "Q3") (pin "1") (pinfunction "G_1") (pintype "passive"))
      (node (ref "U1") (pin "18") (pinfunction "GHC_18") (pintype "output"))
    )
    (net (code "13") (name "/GLA") (class "Default")
      (node (ref "C48") (pin "1") (pinfunction "1_1") (pintype "passive"))
      (node (ref "Q4") (pin "1") (pinfunction "G_1") (pintype "passive"))
      (node (ref "U1") (pin "10") (pinfunction "GLA_10") (pintype "output"))
    )
    (net (code "14") (name "/GLB") (class "Default")
      (node (ref "C49") (pin "1") (pinfunction "1_1") (pintype "passive"))
      (node (ref "Q5") (pin "1") (pinfunction "G_1") (pintype "passive"))
      (node (ref "U1") (pin "15") (pinfunction "GLB_15") (pintype "output"))
    )
    (net (code "15") (name "/GLC") (class "Default")
      (node (ref "C47") (pin "1") (pinfunction "1_1") (pintype "passive"))
      (node (ref "Q6") (pin "1") (pinfunction "G_1") (pintype "passive"))
      (node (ref "U1") (pin "20") (pinfunction "GLC_20") (pintype "output"))
    )
    (net (code "16") (name "/IA_IDC") (class "Default")
      (node (ref "C23") (pin "1") (pinfunction "1_1") (pintype "passive"))
      (node (ref "R23") (pin "2") (pinfunction "2_2") (pintype "passive"))
    )
    (net (code "17") (name "/INH_A") (class "Default")
      (node (ref "U1") (pin "34") (pinfunction "INHA_34") (pintype "input"))
    )
    (net (code "18") (name "/INH_B") (class "Default")
      (node (ref "U1") (pin "36") (pinfunction "INHB_36") (pintype "input"))
    )
    (net (code "19") (name "/INH_C") (class "Default")
      (node (ref "U1") (pin "38") (pinfunction "INHC_38") (pintype "input"))
    )
    (net (code "20") (name "/INL_A") (class "Default")
      (node (ref "U1") (pin "35") (pinfunction "INLA_35") (pintype "input"))
    )
    (net (code "21") (name "/INL_B") (class "Default")
      (node (ref "U1") (pin "37") (pinfunction "INLB_37") (pintype "input"))
    )
    (net (code "22") (name "/INL_C") (class "Default")
      (node (ref "U1") (pin "39") (pinfunction "INLC_39") (pintype "input"))
    )
    (net (code "23") (name "/POWER_ON") (class "Default")
      (node (ref "R49") (pin "2") (pinfunction "2_2") (pintype "passive"))
    )
    (net (code "24") (name "/SCLK") (class "Default")
      (node (ref "R17") (pin "1") (pinfunction "1_1") (pintype "passive"))
    )
    (net (code "25") (name "/SCS") (class "Default")
      (node (ref "U1") (pin "32") (pinfunction "NC~{/}SCS_32") (pintype "input"))
    )
    (net (code "26") (name "/SDI") (class "Default")
      (node (ref "R13") (pin "1") (pinfunction "1_1") (pintype "passive"))
    )
    (net (code "27") (name "/SDO") (class "Default")
      (node (ref "R9") (pin "1") (pinfunction "1_1") (pintype "passive"))
    )
    (net (code "28") (name "/SHA") (class "Default")
      (node (ref "C13") (pin "2") (pinfunction "2_2") (pintype "passive"))
      (node (ref "C16") (pin "1") (pinfunction "1_1") (pintype "passive"))
      (node (ref "C20") (pin "2") (pinfunction "2_2") (pintype "passive"))
      (node (ref "Q1") (pin "3") (pinfunction "S_3") (pintype "passive"))
      (node (ref "Q4") (pin "2") (pinfunction "D_2") (pintype "passive"))
      (node (ref "R36") (pin "2") (pinfunction "2_2") (pintype "passive"))
      (node (ref "U1") (pin "9") (pinfunction "SHA_9") (pintype "input"))
    )
    (net (code "29") (name "/SHB") (class "Default")
      (node (ref "C14") (pin "2") (pinfunction "2_2") (pintype "passive"))
      (node (ref "C17") (pin "1") (pinfunction "1_1") (pintype "passive"))
      (node (ref "C22") (pin "2") (pinfunction "2_2") (pintype "passive"))
      (node (ref "Q2") (pin "3") (pinfunction "S_3") (pintype "passive"))
      (node (ref "Q5") (pin "2") (pinfunction "D_2") (pintype "passive"))
      (node (ref "R37") (pin "2") (pinfunction "2_2") (pintype "passive"))
      (node (ref "U1") (pin "16") (pinfunction "SHB_16") (pintype "input"))
    )
    (net (code "30") (name "/SHC") (class "Default")
      (node (ref "C15") (pin "2") (pinfunction "2_2") (pintype "passive"))
      (node (ref "C18") (pin "1") (pinfunction "1_1") (pintype "passive"))
      (node (ref "C46") (pin "2") (pinfunction "2_2") (pintype "passive"))
      (node (ref "Q3") (pin "3") (pinfunction "S_3") (pintype "passive"))
      (node (ref "Q6") (pin "2") (pinfunction "D_2") (pintype "passive"))
      (node (ref "R38") (pin "2") (pinfunction "2_2") (pintype "passive"))
      (node (ref "U1") (pin "19") (pinfunction "SHC_19") (pintype "input"))
    )
    (net (code "31") (name "/SLA") (class "Default")
      (node (ref "C10") (pin "2") (pinfunction "2_2") (pintype "passive"))
      (node (ref "C11") (pin "2") (pinfunction "2_2") (pintype "passive"))
      (node (ref "C12") (pin "2") (pinfunction "2_2") (pintype "passive"))
      (node (ref "C47") (pin "2") (pinfunction "2_2") (pintype "passive"))
      (node (ref "C48") (pin "2") (pinfunction "2_2") (pintype "passive"))
      (node (ref "C49") (pin "2") (pinfunction "2_2") (pintype "passive"))
      (node (ref "Q4") (pin "3") (pinfunction "S_3") (pintype "passive"))
      (node (ref "Q5") (pin "3") (pinfunction "S_3") (pintype "passive"))
      (node (ref "Q6") (pin "3") (pinfunction "S_3") (pintype "passive"))
      (node (ref "R14") (pin "1") (pinfunction "1_1") (pintype "passive"))
      (node (ref "R15") (pin "1") (pinfunction "1_1") (pintype "passive"))
      (node (ref "R16") (pin "1") (pinfunction "1_1") (pintype "passive"))
      (node (ref "R22") (pin "1") (pinfunction "1_1") (pintype "passive"))
      (node (ref "R24") (pin "2") (pinfunction "2_2") (pintype "passive"))
      (node (ref "R25") (pin "2") (pinfunction "2_2") (pintype "passive"))
      (node (ref "U1") (pin "11") (pinfunction "SLA_11") (pintype "input"))
      (node (ref "U1") (pin "14") (pinfunction "SLB_14") (pintype "input"))
      (node (ref "U1") (pin "21") (pinfunction "SLC_21") (pintype "input"))
    )
    (net (code "32") (name "/VIN") (class "Default")
      (node (ref "C29") (pin "1") (pinfunction "1_1") (pintype "passive"))
      (node (ref "C30") (pin "1") (pinfunction "1_1") (pintype "passive"))
      (node (ref "L2") (pin "2") (pinfunction "2_2") (pintype "passive"))
      (node (ref "R32") (pin "1") (pinfunction "1_1") (pintype "passive"))
      (node (ref "U1") (pin "43") (pinfunction "VIN_43") (pintype "power_in"))
    )
    (net (code "33") (name "3.3V") (class "Default")
      (node (ref "C19") (pin "2") (pinfunction "2_2") (pintype "passive"))
      (node (ref "R66") (pin "2") (pinfunction "2_2") (pintype "passive"))
      (node (ref "R7") (pin "2") (pinfunction "2_2") (pintype "passive"))
      (node (ref "U5") (pin "5") (pinfunction "VS_5") (pintype "power_in"))
    )
    (net (code "34") (name "15V") (class "Default")
      (node (ref "J2") (pin "1") (pinfunction "1_1") (pintype "passive"))
      (node (ref "R28") (pin "2") (pinfunction "2_2") (pintype "passive"))
    )
    (net (code "35") (name "DVDD") (class "Default")
      (node (ref "C9") (pin "1") (pinfunction "1_1") (pintype "passive"))
      (node (ref "R5") (pin "1") (pinfunction "1_1") (pintype "passive"))
      (node (ref "R8") (pin "1") (pinfunction "1_1") (pintype "passive"))
      (node (ref "U1") (pin "40") (pinfunction "DVDD_40") (pintype "power_in"))
    )
    (net (code "36") (name "GND") (class "Default")
      (node (ref "C1") (pin "2") (pinfunction "-_2") (pintype "passive"))
      (node (ref "C19") (pin "1") (pinfunction "1_1") (pintype "passive"))
      (node (ref "C2") (pin "2") (pinfunction "-_2") (pintype "passive"))
      (node (ref "C23") (pin "2") (pinfunction "2_2") (pintype "passive"))
      (node (ref "C27") (pin "2") (pinfunction "2_2") (pintype "passive"))
      (node (ref "C28") (pin "2") (pinfunction "2_2") (pintype "passive"))
      (node (ref "C29") (pin "2") (pinfunction "2_2") (pintype "passive"))
      (node (ref "C3") (pin "2") (pinfunction "2_2") (pintype "passive"))
      (node (ref "C30") (pin "2") (pinfunction "2_2") (pintype "passive"))
      (node (ref "C31") (pin "2") (pinfunction "2_2") (pintype "passive"))
      (node (ref "C32") (pin "2") (pinfunction "2_2") (pintype "passive"))
      (node (ref "C33") (pin "2") (pinfunction "2_2") (pintype "passive"))
      (node (ref "C4") (pin "2") (pinfunction "2_2") (pintype "passive"))
      (node (ref "C5") (pin "2") (pinfunction "2_2") (pintype "passive"))
      (node (ref "C6") (pin "2") (pinfunction "2_2") (pintype "passive"))
      (node (ref "C9") (pin "2") (pinfunction "2_2") (pintype "passive"))
      (node (ref "D1") (pin "1") (pinfunction "1_1") (pintype "passive"))
      (node (ref "D2") (pin "2") (pinfunction "A_2") (pintype "passive"))
      (node (ref "D4") (pin "1") (pinfunction "K_1") (pintype "passive"))
      (node (ref "Q8") (pin "2") (pinfunction "E_2") (pintype "passive"))
      (node (ref "R10") (pin "1") (pinfunction "1_1") (pintype "passive"))
      (node (ref "R24") (pin "1") (pinfunction "1_1") (pintype "passive"))
      (node (ref "R25") (pin "1") (pinfunction "1_1") (pintype "passive"))
      (node (ref "R27") (pin "1") (pinfunction "1_1") (pintype "passive"))
      (node (ref "R31") (pin "1") (pinfunction "1_1") (pintype "passive"))
      (node (ref "R33") (pin "1") (pinfunction "1_1") (pintype "passive"))
      (node (ref "R34") (pin "1") (pinfunction "1_1") (pintype "passive"))
      (node (ref "R4") (pin "2") (pinfunction "2_2") (pintype "passive"))
      (node (ref "R47") (pin "1") (pinfunction "1_1") (pintype "passive"))
      (node (ref "R6") (pin "1") (pinfunction "1_1") (pintype "passive"))
      (node (ref "U1") (pin "1") (pinfunction "PGND_1") (pintype "power_in"))
      (node (ref "U1") (pin "27") (pinfunction "AGND_27") (pintype "power_in"))
      (node (ref "U1") (pin "41") (pinfunction "DGND_41") (pintype "power_in"))
      (node (ref "U1") (pin "49") (pinfunction "PAD_49") (pintype "power_in"))
      (node (ref "U5") (pin "2") (pinfunction "GND_2") (pintype "power_in"))
    )
    (net (code "37") (name "Net-(C13-Pad1)") (class "Default")
      (node (ref "C13") (pin "1") (pinfunction "1_1") (pintype "passive"))
      (node (ref "R1") (pin "1") (pinfunction "1_1") (pintype "passive"))
    )
    (net (code "38") (name "Net-(C14-Pad1)") (class "Default")
      (node (ref "C14") (pin "1") (pinfunction "1_1") (pintype "passive"))
      (node (ref "R2") (pin "1") (pinfunction "1_1") (pintype "passive"))
    )
    (net (code "39") (name "Net-(C15-Pad1)") (class "Default")
      (node (ref "C15") (pin "1") (pinfunction "1_1") (pintype "passive"))
      (node (ref "R3") (pin "1") (pinfunction "1_1") (pintype "passive"))
    )
    (net (code "40") (name "Net-(C16-Pad2)") (class "Default")
      (node (ref "C16") (pin "2") (pinfunction "2_2") (pintype "passive"))
      (node (ref "R14") (pin "2") (pinfunction "2_2") (pintype "passive"))
    )
    (net (code "41") (name "Net-(C17-Pad2)") (class "Default")
      (node (ref "C17") (pin "2") (pinfunction "2_2") (pintype "passive"))
      (node (ref "R15") (pin "2") (pinfunction "2_2") (pintype "passive"))
    )
    (net (code "42") (name "Net-(C18-Pad2)") (class "Default")
      (node (ref "C18") (pin "2") (pinfunction "2_2") (pintype "passive"))
      (node (ref "R16") (pin "2") (pinfunction "2_2") (pintype "passive"))
    )
    (net (code "43") (name "Net-(C25-Pad1)") (class "Default")
      (node (ref "C25") (pin "1") (pinfunction "1_1") (pintype "passive"))
      (node (ref "C26") (pin "1") (pinfunction "1_1") (pintype "passive"))
      (node (ref "L1") (pin "2") (pinfunction "2_2") (pintype "passive"))
      (node (ref "R28") (pin "1") (pinfunction "1_1") (pintype "passive"))
      (node (ref "R29") (pin "2") (pinfunction "2_2") (pintype "passive"))
      (node (ref "R30") (pin "2") (pinfunction "2_2") (pintype "passive"))
    )
    (net (code "44") (name "Net-(C26-Pad2)") (class "Default")
      (node (ref "C26") (pin "2") (pinfunction "2_2") (pintype "passive"))
      (node (ref "R31") (pin "2") (pinfunction "2_2") (pintype "passive"))
    )
    (net (code "45") (name "Net-(D2-K)") (class "Default")
      (node (ref "C24") (pin "2") (pinfunction "2_2") (pintype "passive"))
      (node (ref "D2") (pin "1") (pinfunction "K_1") (pintype "passive"))
      (node (ref "L1") (pin "1") (pinfunction "1_1") (pintype "passive"))
      (node (ref "U1") (pin "42") (pinfunction "SW_42") (pintype "power_in"))
    )
    (net (code "46") (name "Net-(D3-K)") (class "Default")
      (node (ref "C27") (pin "1") (pinfunction "1_1") (pintype "passive"))
      (node (ref "C28") (pin "1") (pinfunction "1_1") (pintype "passive"))
      (node (ref "D3") (pin "1") (pinfunction "K_1") (pintype "passive"))
      (node (ref "L2") (pin "1") (pinfunction "1_1") (pintype "passive"))
    )
    (net (code "47") (name "Net-(D4-A)") (class "Default")
      (node (ref "D4") (pin "2") (pinfunction "A_2") (pintype "passive"))
      (node (ref "R30") (pin "1") (pinfunction "1_1") (pintype "passive"))
    )
    (net (code "48") (name "Net-(Q7-B)") (class "Default")
      (node (ref "Q7") (pin "1") (pinfunction "B_1") (pintype "passive"))
      (node (ref "R43") (pin "1") (pinfunction "1_1") (pintype "passive"))
      (node (ref "R48") (pin "2") (pinfunction "2_2") (pintype "passive"))
    )
    (net (code "49") (name "Net-(Q8-B)") (class "Default")
      (node (ref "Q8") (pin "1") (pinfunction "B_1") (pintype "passive"))
      (node (ref "R49") (pin "1") (pinfunction "1_1") (pintype "passive"))
    )
    (net (code "50") (name "Net-(Q8-C)") (class "Default")
      (node (ref "Q8") (pin "3") (pinfunction "C_3") (pintype "passive"))
      (node (ref "R48") (pin "1") (pinfunction "1_1") (pintype "passive"))
    )
    (net (code "51") (name "Net-(R35-Pad1)") (class "Default")
      (node (ref "R35") (pin "1") (pinfunction "1_1") (pintype "passive"))
      (node (ref "R39") (pin "2") (pinfunction "2_2") (pintype "passive"))
    )
    (net (code "52") (name "Net-(R36-Pad1)") (class "Default")
      (node (ref "R36") (pin "1") (pinfunction "1_1") (pintype "passive"))
      (node (ref "R40") (pin "2") (pinfunction "2_2") (pintype "passive"))
    )
    (net (code "53") (name "Net-(R37-Pad1)") (class "Default")
      (node (ref "R37") (pin "1") (pinfunction "1_1") (pintype "passive"))
      (node (ref "R41") (pin "2") (pinfunction "2_2") (pintype "passive"))
    )
    (net (code "54") (name "Net-(R38-Pad1)") (class "Default")
      (node (ref "R38") (pin "1") (pinfunction "1_1") (pintype "passive"))
      (node (ref "R42") (pin "2") (pinfunction "2_2") (pintype "passive"))
    )
    (net (code "55") (name "Net-(U1-BST)") (class "Default")
      (node (ref "C24") (pin "1") (pinfunction "1_1") (pintype "passive"))
      (node (ref "U1") (pin "45") (pinfunction "BST_45") (pintype "power_in"))
    )
    (net (code "56") (name "Net-(U1-CPH)") (class "Default")
      (node (ref "C8") (pin "2") (pinfunction "2_2") (pintype "passive"))
      (node (ref "U1") (pin "4") (pinfunction "CPH_4") (pintype "power_in"))
    )
    (net (code "57") (name "Net-(U1-CPL)") (class "Default")
      (node (ref "C8") (pin "1") (pinfunction "1_1") (pintype "passive"))
      (node (ref "U1") (pin "3") (pinfunction "CPL_3") (pintype "power_in"))
    )
    (net (code "58") (name "Net-(U1-FB)") (class "Default")
      (node (ref "C25") (pin "2") (pinfunction "2_2") (pintype "passive"))
      (node (ref "R29") (pin "1") (pinfunction "1_1") (pintype "passive"))
      (node (ref "R34") (pin "2") (pinfunction "2_2") (pintype "passive"))
      (node (ref "U1") (pin "48") (pinfunction "FB_48") (pintype "input"))
    )
    (net (code "59") (name "Net-(U1-IDRIVE{slash}SDI)") (class "Default")
      (node (ref "R13") (pin "2") (pinfunction "2_2") (pintype "passive"))
      (node (ref "R5") (pin "2") (pinfunction "2_2") (pintype "passive"))
      (node (ref "R6") (pin "2") (pinfunction "2_2") (pintype "passive"))
      (node (ref "U1") (pin "30") (pinfunction "IDRIVE/SDI_30") (pintype "input"))
    )
    (net (code "60") (name "Net-(U1-MODE{slash}SDO)") (class "Default")
      (node (ref "R4") (pin "1") (pinfunction "1_1") (pintype "passive"))
      (node (ref "R7") (pin "1") (pinfunction "1_1") (pintype "passive"))
      (node (ref "R9") (pin "2") (pinfunction "2_2") (pintype "passive"))
      (node (ref "U1") (pin "29") (pinfunction "MODE/SDO_29") (pintype "bidirectional"))
    )
    (net (code "61") (name "Net-(U1-RCL)") (class "Default")
      (node (ref "R33") (pin "2") (pinfunction "2_2") (pintype "passive"))
      (node (ref "U1") (pin "46") (pinfunction "RCL_46") (pintype "input"))
    )
    (net (code "62") (name "Net-(U1-RT{slash}SD)") (class "Default")
      (node (ref "R32") (pin "2") (pinfunction "2_2") (pintype "passive"))
      (node (ref "U1") (pin "47") (pinfunction "RT/SD_47") (pintype "input"))
    )
    (net (code "63") (name "Net-(U1-VCP)") (class "Default")
      (node (ref "C7") (pin "1") (pinfunction "1_1") (pintype "passive"))
      (node (ref "U1") (pin "7") (pinfunction "VCP_7") (pintype "power_in"))
    )
    (net (code "64") (name "Net-(U1-VDS{slash}SCLK)") (class "Default")
      (node (ref "R10") (pin "2") (pinfunction "2_2") (pintype "passive"))
      (node (ref "R17") (pin "2") (pinfunction "2_2") (pintype "passive"))
      (node (ref "R8") (pin "2") (pinfunction "2_2") (pintype "passive"))
      (node (ref "U1") (pin "31") (pinfunction "VDS/SCLK_31") (pintype "input"))
    )
    (net (code "65") (name "Net-(U1-VGLS)") (class "Default")
      (node (ref "C31") (pin "1") (pinfunction "1_1") (pintype "passive"))
      (node (ref "U1") (pin "2") (pinfunction "VGLS_2") (pintype "power_in"))
    )
    (net (code "66") (name "Net-(U1-VM)") (class "Default")
      (node (ref "C5") (pin "1") (pinfunction "1_1") (pintype "passive"))
      (node (ref "C6") (pin "1") (pinfunction "1_1") (pintype "passive"))
      (node (ref "J1") (pin "2") (pinfunction "2_2") (pintype "passive"))
      (node (ref "J2") (pin "2") (pinfunction "2_2") (pintype "passive"))
      (node (ref "U1") (pin "5") (pinfunction "VM_5") (pintype "power_in"))
    )
    (net (code "67") (name "Net-(U5-IN+)") (class "Default")
      (node (ref "C21") (pin "1") (pinfunction "1_1") (pintype "passive"))
      (node (ref "R22") (pin "2") (pinfunction "2_2") (pintype "passive"))
      (node (ref "U5") (pin "3") (pinfunction "IN+_3") (pintype "input"))
    )
    (net (code "68") (name "Net-(U5-IN-)") (class "Default")
      (node (ref "C21") (pin "2") (pinfunction "2_2") (pintype "passive"))
      (node (ref "R27") (pin "2") (pinfunction "2_2") (pintype "passive"))
      (node (ref "U5") (pin "4") (pinfunction "IN-_4") (pintype "input"))
    )
    (net (code "69") (name "Net-(U5-OUT)") (class "Default")
      (node (ref "R23") (pin "1") (pinfunction "1_1") (pintype "passive"))
      (node (ref "U5") (pin "1") (pinfunction "OUT_1") (pintype "output"))
    )
    (net (code "70") (name "VCC") (class "Default")
      (node (ref "C32") (pin "1") (pinfunction "1_1") (pintype "passive"))
      (node (ref "U1") (pin "44") (pinfunction "VCC_44") (pintype "power_in"))
    )
    (net (code "71") (name "VDC") (class "Default")
      (node (ref "C1") (pin "1") (pinfunction "+_1") (pintype "passive"))
      (node (ref "C10") (pin "1") (pinfunction "1_1") (pintype "passive"))
      (node (ref "C11") (pin "1") (pinfunction "1_1") (pintype "passive"))
      (node (ref "C12") (pin "1") (pinfunction "1_1") (pintype "passive"))
      (node (ref "C2") (pin "1") (pinfunction "+_1") (pintype "passive"))
      (node (ref "C3") (pin "1") (pinfunction "1_1") (pintype "passive"))
      (node (ref "C4") (pin "1") (pinfunction "1_1") (pintype "passive"))
      (node (ref "C7") (pin "2") (pinfunction "2_2") (pintype "passive"))
      (node (ref "D1") (pin "2") (pinfunction "2_2") (pintype "passive"))
      (node (ref "J3") (pin "1") (pinfunction "1_1") (pintype "passive"))
      (node (ref "Q1") (pin "2") (pinfunction "D_2") (pintype "passive"))
      (node (ref "Q2") (pin "2") (pinfunction "D_2") (pintype "passive"))
      (node (ref "Q3") (pin "2") (pinfunction "D_2") (pintype "passive"))
      (node (ref "Q7") (pin "2") (pinfunction "E_2") (pintype "passive"))
      (node (ref "R1") (pin "2") (pinfunction "2_2") (pintype "passive"))
      (node (ref "R2") (pin "2") (pinfunction "2_2") (pintype "passive"))
      (node (ref "R3") (pin "2") (pinfunction "2_2") (pintype "passive"))
      (node (ref "R43") (pin "2") (pinfunction "2_2") (pintype "passive"))
      (node (ref "U1") (pin "6") (pinfunction "VDRAIN_6") (pintype "input"))
    )
    (net (code "72") (name "VGD") (class "Default")
      (node (ref "D3") (pin "2") (pinfunction "A_2") (pintype "passive"))
      (node (ref "J1") (pin "1") (pinfunction "1_1") (pintype "passive"))
      (node (ref "J3") (pin "2") (pinfunction "2_2") (pintype "passive"))
      (node (ref "Q7") (pin "3") (pinfunction "C_3") (pintype "passive"))
      (node (ref "R35") (pin "2") (pinfunction "2_2") (pintype "passive"))
    )
    (net (code "73") (name "unconnected-(U1-NC-Pad12)") (class "Default")
      (node (ref "U1") (pin "12") (pinfunction "NC_12") (pintype "passive"))
    )
    (net (code "74") (name "unconnected-(U1-NC-Pad13)") (class "Default")
      (node (ref "U1") (pin "13") (pinfunction "NC_13") (pintype "passive"))
    )
    (net (code "75") (name "unconnected-(U1-NC-Pad22)") (class "Default")
      (node (ref "U1") (pin "22") (pinfunction "NC_22") (pintype "passive"))
    )
    (net (code "76") (name "unconnected-(U1-NC-Pad23)") (class "Default")
      (node (ref "U1") (pin "23") (pinfunction "NC_23") (pintype "passive"))
    )
    (net (code "77") (name "unconnected-(U1-NC-Pad24)") (class "Default")
      (node (ref "U1") (pin "24") (pinfunction "NC_24") (pintype "passive"))
    )
    (net (code "78") (name "unconnected-(U1-NC-Pad25)") (class "Default")
      (node (ref "U1") (pin "25") (pinfunction "NC_25") (pintype "passive"))
    )
    (net (code "79") (name "unconnected-(U1-NC-Pad26)") (class "Default")
      (node (ref "U1") (pin "26") (pinfunction "NC_26") (pintype "passive"))
    )
  )
)
